# MStar-WLAN.net
KiCad netlist of a schematic drawn in EAGLE
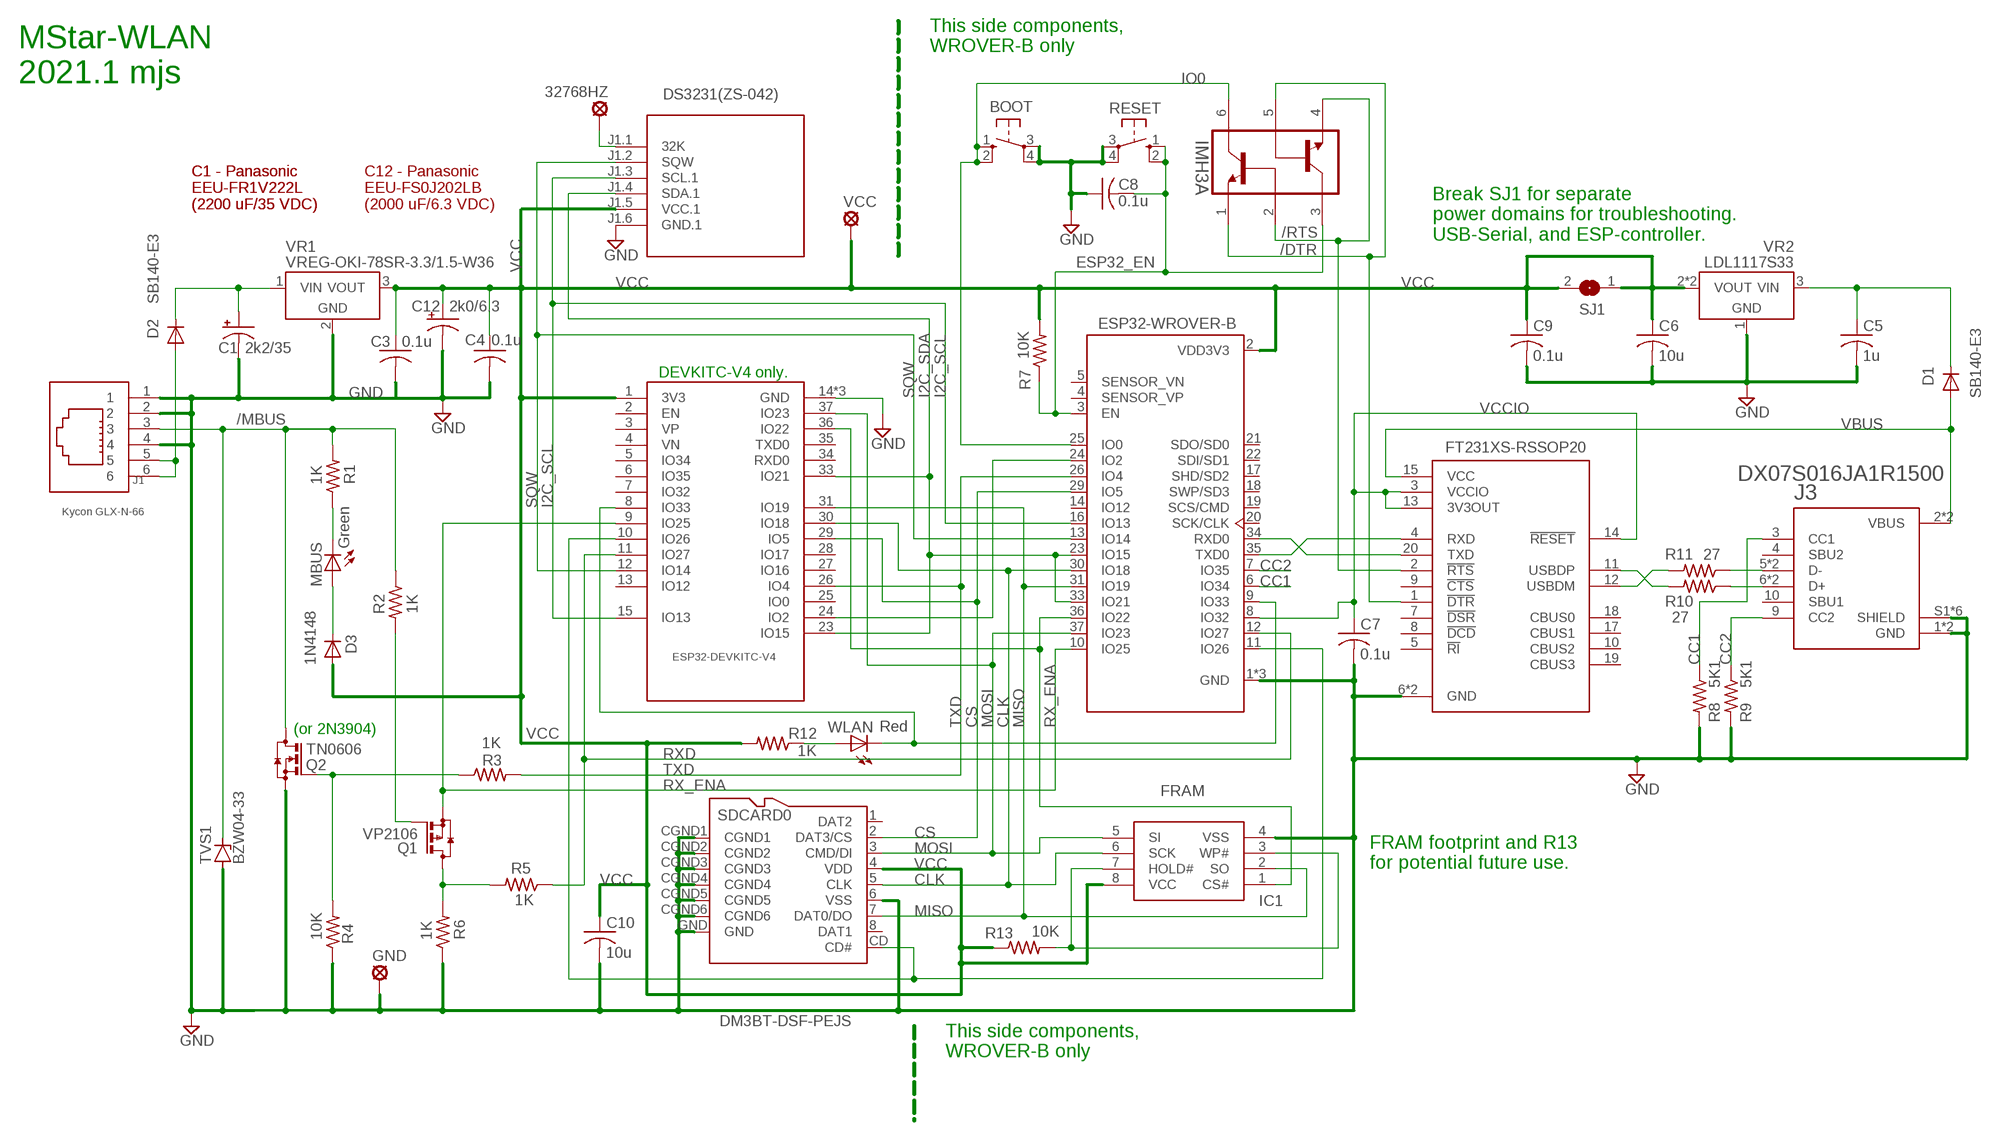
[diagram p0: schematic, sheet 1]

(export (version "E")
  (design (tool "Eeschema 10.0.6"))
  (components
    (comp (ref "32768HZ")
      (value "MCS10B")
      (footprint "eagle-import:MCS10B")
      (libsource (lib "eagle-import") (part "MCS10B"))
    )
    (comp (ref "BOOT")
      (value "PTS645SM432LFS")
      (footprint "eagle-import:B3F-10XX")
      (fields (field (name "MPN") "B3F-1000"))
      (libsource (lib "eagle-import") (part "10-XX"))
    )
    (comp (ref "C1")
      (value "2k2/35")
      (footprint "eagle-import:E5-4")
      (libsource (lib "eagle-import") (part "CPOL-USE5-4"))
    )
    (comp (ref "C3")
      (value "0.1u")
      (footprint "eagle-import:C025-024X044")
      (libsource (lib "eagle-import") (part "C-US025-024X044"))
    )
    (comp (ref "C4")
      (value "0.1u")
      (footprint "eagle-import:C025-024X044")
      (libsource (lib "eagle-import") (part "C-US025-024X044"))
    )
    (comp (ref "C5")
      (value "1u")
      (footprint "eagle-import:C1206")
      (libsource (lib "eagle-import") (part "C-USC1206"))
    )
    (comp (ref "C6")
      (value "10u")
      (footprint "eagle-import:C1206")
      (libsource (lib "eagle-import") (part "C-USC1206"))
    )
    (comp (ref "C7")
      (value "0.1u")
      (footprint "eagle-import:C025-024X044")
      (libsource (lib "eagle-import") (part "C-US025-024X044"))
    )
    (comp (ref "C8")
      (value "0.1u")
      (footprint "eagle-import:C025-024X044")
      (libsource (lib "eagle-import") (part "C-US025-024X044"))
    )
    (comp (ref "C9")
      (value "0.1u")
      (footprint "eagle-import:C025-024X044")
      (libsource (lib "eagle-import") (part "C-US025-024X044"))
    )
    (comp (ref "C10")
      (value "10u")
      (footprint "eagle-import:C1206")
      (libsource (lib "eagle-import") (part "C-USC1206"))
    )
    (comp (ref "C12")
      (value "2k0/6.3")
      (footprint "eagle-import:E5-6")
      (libsource (lib "eagle-import") (part "CPOL-USE5-6"))
    )
    (comp (ref "D1")
      (value "SB140-E3")
      (footprint "eagle-import:DO41-7.6")
      (libsource (lib "eagle-import") (part "DIODE-DO41-7.6"))
    )
    (comp (ref "D2")
      (value "SB140-E3")
      (footprint "eagle-import:DO41-7.6")
      (libsource (lib "eagle-import") (part "DIODE-DO41-7.6"))
    )
    (comp (ref "D3")
      (value "1N4148")
      (footprint "eagle-import:DO35-7")
      (libsource (lib "eagle-import") (part "1N4148DO35-7"))
    )
    (comp (ref "DS3231(ZS-042)")
      (value "RTC-DS3231-AT24C32-6")
      (footprint "eagle-import:RTC-DS3231-AT24C32-6")
      (libsource (lib "eagle-import") (part "RTC-DS3231-AT24C32-6"))
    )
    (comp (ref "ESP32-WROVER-B")
      (value "ESP32-WROVER-I")
      (footprint "eagle-import:XCVR_ESP32-WROVER-I")
      (fields (field (name "MF") "Espressif Systems"))
      (libsource (lib "eagle-import") (part "ESP32-WROVER-I"))
    )
    (comp (ref "FT231XS")
      (value "FT231XS-RSSOP20")
      (footprint "eagle-import:SSOP20")
      (fields
        (field (name "DIGI-KEY_PART_NUMBER") "768-1129-1-ND")
        (field (name "MF") "FTDI,")
        (field (name "MP") "FT231XS-R")
      )
      (libsource (lib "eagle-import") (part "FT231XS-RSSOP20"))
    )
    (comp (ref "GND")
      (value "MCS10B")
      (footprint "eagle-import:MCS10B")
      (libsource (lib "eagle-import") (part "MCS10B"))
    )
    (comp (ref "IC1")
      (value "FRAM")
      (footprint "eagle-import:SO-08M")
      (libsource (lib "eagle-import") (part "MR45V100AMAZAATLSO8M"))
    )
    (comp (ref "IMH3A")
      (value "IMH3ATSOP6")
      (footprint "eagle-import:TSOP6")
      (libsource (lib "eagle-import") (part "IMH3ATSOP6"))
    )
    (comp (ref "J1")
      (value "Kycon GLX-N-66")
      (footprint "eagle-import:6P6C")
      (libsource (lib "eagle-import") (part "6P6C"))
    )
    (comp (ref "J3")
      (value "DX07S016JA1R1500")
      (footprint "eagle-import:JAE_DX07S016JA1R1500")
      (fields (field (name "MF") "JAE Electronics"))
      (libsource (lib "eagle-import") (part "DX07S016JA1R1500"))
    )
    (comp (ref "MBUS")
      (value "Green")
      (footprint "eagle-import:LED3MM")
      (libsource (lib "eagle-import") (part "LED3MM"))
    )
    (comp (ref "Q1")
      (value "VP2106")
      (footprint "eagle-import:TO92")
      (libsource (lib "eagle-import") (part "VP2106"))
    )
    (comp (ref "Q2")
      (value "TN0606")
      (footprint "eagle-import:TO92")
      (libsource (lib "eagle-import") (part "TN0606"))
    )
    (comp (ref "R1")
      (value "1K")
      (footprint "eagle-import:0204_5")
      (libsource (lib "eagle-import") (part "R-US_"))
    )
    (comp (ref "R2")
      (value "1K")
      (footprint "eagle-import:0204_5")
      (libsource (lib "eagle-import") (part "R-US_"))
    )
    (comp (ref "R3")
      (value "1K")
      (footprint "eagle-import:0204_5")
      (libsource (lib "eagle-import") (part "R-US_"))
    )
    (comp (ref "R4")
      (value "10K")
      (footprint "eagle-import:0204_5")
      (libsource (lib "eagle-import") (part "R-US_"))
    )
    (comp (ref "R5")
      (value "1K")
      (footprint "eagle-import:0204_5")
      (libsource (lib "eagle-import") (part "R-US_"))
    )
    (comp (ref "R6")
      (value "1K")
      (footprint "eagle-import:0204_5")
      (libsource (lib "eagle-import") (part "R-US_"))
    )
    (comp (ref "R7")
      (value "10K")
      (footprint "eagle-import:0204_5")
      (libsource (lib "eagle-import") (part "R-US_"))
    )
    (comp (ref "R8")
      (value "5K1")
      (footprint "eagle-import:0204_5")
      (libsource (lib "eagle-import") (part "R-US_"))
    )
    (comp (ref "R9")
      (value "5K1")
      (footprint "eagle-import:0204_5")
      (libsource (lib "eagle-import") (part "R-US_"))
    )
    (comp (ref "R10")
      (value "27")
      (footprint "eagle-import:0204_5")
      (libsource (lib "eagle-import") (part "R-US_"))
    )
    (comp (ref "R11")
      (value "27")
      (footprint "eagle-import:0204_5")
      (libsource (lib "eagle-import") (part "R-US_"))
    )
    (comp (ref "R12")
      (value "1K")
      (footprint "eagle-import:0204_5")
      (libsource (lib "eagle-import") (part "R-US_"))
    )
    (comp (ref "R13")
      (value "10K")
      (footprint "eagle-import:R1206")
      (libsource (lib "eagle-import") (part "R-US_R1206"))
    )
    (comp (ref "RESET")
      (value "PTS645SM432LFS")
      (footprint "eagle-import:B3F-10XX")
      (fields (field (name "MPN") "B3F-1000"))
      (libsource (lib "eagle-import") (part "10-XX"))
    )
    (comp (ref "SDCARD0")
      (value "DM3BT-DSF-PEJS")
      (footprint "eagle-import:DM3BT-DSF-PEJS")
      (fields (field (name "MF") "Hirose"))
      (libsource (lib "eagle-import") (part "DM3BT-DSF-PEJS"))
    )
    (comp (ref "SJ1") (value "SJ") (footprint "eagle-import:SJ") (libsource (lib "eagle-import") (part "SJ")))
    (comp (ref "TVS1")
      (value "BZW04-33")
      (footprint "eagle-import:DO41Z10")
      (libsource (lib "eagle-import") (part "ZPY"))
    )
    (comp (ref "U$1")
      (value "ESP32-DEVKITC-V4-NOSD")
      (footprint "eagle-import:ESP32-DEVKITC-V4-NOSD")
      (libsource (lib "eagle-import") (part "ESP32-DEVKITC-V4-NOSD"))
    )
    (comp (ref "VCC")
      (value "MCS10B")
      (footprint "eagle-import:MCS10B")
      (libsource (lib "eagle-import") (part "MCS10B"))
    )
    (comp (ref "VR1")
      (value "VREG-OKI-78SR-3.3/1.5-W36")
      (footprint "eagle-import:OKI-78SR")
      (libsource (lib "eagle-import") (part "VREG-OKI-78SR-3.3/1.5-W36"))
    )
    (comp (ref "VR2")
      (value "LDL1117S33")
      (footprint "eagle-import:SOT223")
      (libsource (lib "eagle-import") (part "VREG-TS1117CW-3V3"))
    )
    (comp (ref "WLAN")
      (value "Red")
      (footprint "eagle-import:LED3MM")
      (libsource (lib "eagle-import") (part "LED3MM"))
    )
  )
  (nets
    (net (code "1") (name "/CC1") (class "Default")
      (node (ref "ESP32-WROVER-B") (pin "6") (pinfunction "IO34_6") (pintype "input"))
      (node (ref "J3") (pin "3") (pinfunction "CC1_3") (pintype "passive"))
      (node (ref "R8") (pin "1") (pinfunction "1_1") (pintype "passive"))
    )
    (net (code "2") (name "/CC2") (class "Default")
      (node (ref "ESP32-WROVER-B") (pin "7") (pinfunction "IO35_7") (pintype "input"))
      (node (ref "J3") (pin "9") (pinfunction "CC2_9") (pintype "passive"))
      (node (ref "R9") (pin "1") (pinfunction "1_1") (pintype "passive"))
    )
    (net (code "3") (name "/CLK") (class "Default")
      (node (ref "ESP32-WROVER-B") (pin "30") (pinfunction "IO18_30") (pintype "bidirectional"))
      (node (ref "IC1") (pin "6") (pinfunction "SCK_6") (pintype "bidirectional"))
      (node (ref "SDCARD0") (pin "5") (pinfunction "CLK_5") (pintype "bidirectional"))
      (node (ref "U$1") (pin "30") (pinfunction "IO18_30") (pintype "bidirectional"))
    )
    (net (code "4") (name "/CS") (class "Default")
      (node (ref "ESP32-WROVER-B") (pin "29") (pinfunction "IO5_29") (pintype "bidirectional"))
      (node (ref "SDCARD0") (pin "2") (pinfunction "DAT3/CS_2") (pintype "bidirectional"))
      (node (ref "U$1") (pin "29") (pinfunction "IO5_29") (pintype "bidirectional"))
    )
    (net (code "5") (name "/ESP32_EN") (class "Default")
      (node (ref "C8") (pin "2") (pinfunction "2_2") (pintype "passive"))
      (node (ref "ESP32-WROVER-B") (pin "3") (pinfunction "EN_3") (pintype "input"))
      (node (ref "IMH3A") (pin "3") (pinfunction "Q2C_3") (pintype "bidirectional"))
      (node (ref "R7") (pin "1") (pinfunction "1_1") (pintype "passive"))
      (node (ref "RESET") (pin "1") (pinfunction "S_1") (pintype "passive"))
      (node (ref "RESET") (pin "2") (pinfunction "S1_2") (pintype "passive"))
    )
    (net (code "6") (name "/I2C_SCL") (class "Default")
      (node (ref "DS3231(ZS-042)") (pin "J1.3") (pinfunction "SCL.1_J1.3") (pintype "bidirectional"))
      (node (ref "ESP32-WROVER-B") (pin "16") (pinfunction "IO13_16") (pintype "bidirectional"))
      (node (ref "U$1") (pin "15") (pinfunction "IO13_15") (pintype "bidirectional"))
    )
    (net (code "7") (name "/I2C_SDA") (class "Default")
      (node (ref "DS3231(ZS-042)") (pin "J1.4") (pinfunction "SDA.1_J1.4") (pintype "bidirectional"))
      (node (ref "ESP32-WROVER-B") (pin "23") (pinfunction "IO15_23") (pintype "bidirectional"))
      (node (ref "ESP32-WROVER-B") (pin "33") (pinfunction "IO21_33") (pintype "bidirectional"))
      (node (ref "U$1") (pin "23") (pinfunction "IO15_23") (pintype "bidirectional"))
      (node (ref "U$1") (pin "33") (pinfunction "IO21_33") (pintype "bidirectional"))
    )
    (net (code "8") (name "/IO0") (class "Default")
      (node (ref "BOOT") (pin "1") (pinfunction "S_1") (pintype "passive"))
      (node (ref "BOOT") (pin "2") (pinfunction "S1_2") (pintype "passive"))
      (node (ref "ESP32-WROVER-B") (pin "25") (pinfunction "IO0_25") (pintype "bidirectional"))
      (node (ref "IMH3A") (pin "6") (pinfunction "Q1C_6") (pintype "bidirectional"))
    )
    (net (code "9") (name "/MISO") (class "Default")
      (node (ref "ESP32-WROVER-B") (pin "31") (pinfunction "IO19_31") (pintype "bidirectional"))
      (node (ref "IC1") (pin "2") (pinfunction "SO_2") (pintype "bidirectional"))
      (node (ref "SDCARD0") (pin "7") (pinfunction "DAT0/DO_7") (pintype "bidirectional"))
      (node (ref "U$1") (pin "31") (pinfunction "IO19_31") (pintype "bidirectional"))
    )
    (net (code "10") (name "/MOSI") (class "Default")
      (node (ref "ESP32-WROVER-B") (pin "37") (pinfunction "IO23_37") (pintype "bidirectional"))
      (node (ref "IC1") (pin "5") (pinfunction "SI_5") (pintype "bidirectional"))
      (node (ref "SDCARD0") (pin "3") (pinfunction "CMD/DI_3") (pintype "bidirectional"))
      (node (ref "U$1") (pin "37") (pinfunction "IO23_37") (pintype "bidirectional"))
    )
    (net (code "12") (name "/RXD") (class "Default")
      (node (ref "ESP32-WROVER-B") (pin "12") (pinfunction "IO27_12") (pintype "bidirectional"))
      (node (ref "R5") (pin "1") (pinfunction "1_1") (pintype "passive"))
      (node (ref "U$1") (pin "11") (pinfunction "IO27_11") (pintype "bidirectional"))
    )
    (net (code "13") (name "/RX_ENA") (class "Default")
      (node (ref "ESP32-WROVER-B") (pin "10") (pinfunction "IO25_10") (pintype "bidirectional"))
      (node (ref "Q1") (pin "S") (pinfunction "S_S") (pintype "passive"))
      (node (ref "U$1") (pin "9") (pinfunction "IO25_9") (pintype "bidirectional"))
    )
    (net (code "14") (name "/SQW") (class "Default")
      (node (ref "DS3231(ZS-042)") (pin "J1.2") (pinfunction "SQW_J1.2") (pintype "bidirectional"))
      (node (ref "ESP32-WROVER-B") (pin "13") (pinfunction "IO14_13") (pintype "bidirectional"))
      (node (ref "U$1") (pin "12") (pinfunction "IO14_12") (pintype "bidirectional"))
    )
    (net (code "15") (name "/TXD") (class "Default")
      (node (ref "ESP32-WROVER-B") (pin "26") (pinfunction "IO4_26") (pintype "bidirectional"))
      (node (ref "R3") (pin "2") (pinfunction "2_2") (pintype "passive"))
      (node (ref "U$1") (pin "26") (pinfunction "IO4_26") (pintype "bidirectional"))
    )
    (net (code "16") (name "/VBUS") (class "Default")
      (node (ref "D1") (pin "A") (pinfunction "A_A") (pintype "passive"))
      (node (ref "FT231XS") (pin "15") (pinfunction "VCC_15") (pintype "power_in"))
      (node (ref "J3") (pin "11") (pinfunction "VBUS_11") (pintype "power_in"))
      (node (ref "J3") (pin "2") (pinfunction "VBUS_2") (pintype "power_in"))
    )
    (net (code "17") (name "/VCC") (class "Default")
      (node (ref "C10") (pin "1") (pinfunction "1_1") (pintype "passive"))
      (node (ref "C12") (pin "+") (pinfunction "+_+") (pintype "passive"))
      (node (ref "C3") (pin "1") (pinfunction "1_1") (pintype "passive"))
      (node (ref "C4") (pin "1") (pinfunction "1_1") (pintype "passive"))
      (node (ref "C6") (pin "1") (pinfunction "1_1") (pintype "passive"))
      (node (ref "C9") (pin "1") (pinfunction "1_1") (pintype "passive"))
      (node (ref "D3") (pin "A") (pinfunction "A_A") (pintype "passive"))
      (node (ref "DS3231(ZS-042)") (pin "J1.5") (pinfunction "VCC.1_J1.5") (pintype "power_in"))
      (node (ref "ESP32-WROVER-B") (pin "2") (pinfunction "VDD3V3_2") (pintype "power_in"))
      (node (ref "IC1") (pin "8") (pinfunction "VCC_8") (pintype "bidirectional"))
      (node (ref "R12") (pin "2") (pinfunction "2_2") (pintype "passive"))
      (node (ref "R13") (pin "1") (pinfunction "1_1") (pintype "passive"))
      (node (ref "R7") (pin "2") (pinfunction "2_2") (pintype "passive"))
      (node (ref "SDCARD0") (pin "4") (pinfunction "VDD_4") (pintype "bidirectional"))
      (node (ref "SJ1") (pin "1") (pinfunction "1_1") (pintype "passive"))
      (node (ref "SJ1") (pin "2") (pinfunction "2_2") (pintype "passive"))
      (node (ref "U$1") (pin "1") (pinfunction "3V3_1") (pintype "power_in"))
      (node (ref "VCC") (pin "MP") (pinfunction "MP_MP") (pintype "passive"))
      (node (ref "VR1") (pin "3") (pinfunction "VOUT_3") (pintype "power_in"))
      (node (ref "VR2") (pin "2") (pinfunction "VOUT_2") (pintype "power_in"))
      (node (ref "VR2") (pin "4") (pinfunction "VOUT_4") (pintype "power_in"))
    )
    (net (code "18") (name "/VCCIO") (class "Default")
      (node (ref "C7") (pin "1") (pinfunction "1_1") (pintype "passive"))
      (node (ref "ESP32-WROVER-B") (pin "8") (pinfunction "IO32_8") (pintype "bidirectional"))
      (node (ref "FT231XS") (pin "13") (pinfunction "3V3OUT_13") (pintype "power_in"))
      (node (ref "FT231XS") (pin "14") (pinfunction "~{RESET}_14") (pintype "input"))
      (node (ref "FT231XS") (pin "3") (pinfunction "VCCIO_3") (pintype "power_in"))
    )
    (net (code "19") (name "/{slash}DTR") (class "Default")
      (node (ref "FT231XS") (pin "1") (pinfunction "~{DTR}_1") (pintype "output"))
      (node (ref "IMH3A") (pin "1") (pinfunction "Q1E_1") (pintype "bidirectional"))
      (node (ref "IMH3A") (pin "5") (pinfunction "Q2B_5") (pintype "bidirectional"))
    )
    (net (code "20") (name "/{slash}MBUS") (class "Default")
      (node (ref "J1") (pin "3") (pinfunction "3_3") (pintype "passive"))
      (node (ref "Q2") (pin "D") (pinfunction "D_D") (pintype "passive"))
      (node (ref "R1") (pin "2") (pinfunction "2_2") (pintype "passive"))
      (node (ref "R2") (pin "1") (pinfunction "1_1") (pintype "passive"))
      (node (ref "TVS1") (pin "C") (pinfunction "C_C") (pintype "passive"))
    )
    (net (code "21") (name "/{slash}RTS") (class "Default")
      (node (ref "FT231XS") (pin "2") (pinfunction "~{RTS}_2") (pintype "output"))
      (node (ref "IMH3A") (pin "2") (pinfunction "Q1B_2") (pintype "bidirectional"))
      (node (ref "IMH3A") (pin "4") (pinfunction "Q2E_4") (pintype "bidirectional"))
    )
    (net (code "22") (name "GND") (class "Default")
      (node (ref "BOOT") (pin "3") (pinfunction "P_3") (pintype "passive"))
      (node (ref "BOOT") (pin "4") (pinfunction "P1_4") (pintype "passive"))
      (node (ref "C1") (pin "-") (pinfunction "-_-") (pintype "passive"))
      (node (ref "C10") (pin "2") (pinfunction "2_2") (pintype "passive"))
      (node (ref "C12") (pin "-") (pinfunction "-_-") (pintype "passive"))
      (node (ref "C3") (pin "2") (pinfunction "2_2") (pintype "passive"))
      (node (ref "C4") (pin "2") (pinfunction "2_2") (pintype "passive"))
      (node (ref "C5") (pin "2") (pinfunction "2_2") (pintype "passive"))
      (node (ref "C6") (pin "2") (pinfunction "2_2") (pintype "passive"))
      (node (ref "C7") (pin "2") (pinfunction "2_2") (pintype "passive"))
      (node (ref "C8") (pin "1") (pinfunction "1_1") (pintype "passive"))
      (node (ref "C9") (pin "2") (pinfunction "2_2") (pintype "passive"))
      (node (ref "DS3231(ZS-042)") (pin "J1.6") (pinfunction "GND.1_J1.6") (pintype "power_in"))
      (node (ref "ESP32-WROVER-B") (pin "1") (pinfunction "GND_1") (pintype "power_in"))
      (node (ref "ESP32-WROVER-B") (pin "15") (pinfunction "GND_15") (pintype "power_in"))
      (node (ref "ESP32-WROVER-B") (pin "38") (pinfunction "GND_38") (pintype "power_in"))
      (node (ref "FT231XS") (pin "16") (pinfunction "GND_16") (pintype "power_in"))
      (node (ref "FT231XS") (pin "6") (pinfunction "GND_6") (pintype "power_in"))
      (node (ref "GND") (pin "MP") (pinfunction "MP_MP") (pintype "passive"))
      (node (ref "IC1") (pin "4") (pinfunction "VSS_4") (pintype "bidirectional"))
      (node (ref "J1") (pin "1") (pinfunction "1_1") (pintype "passive"))
      (node (ref "J1") (pin "2") (pinfunction "2_2") (pintype "passive"))
      (node (ref "J1") (pin "4") (pinfunction "4_4") (pintype "passive"))
      (node (ref "J3") (pin "1") (pinfunction "GND_1") (pintype "power_in"))
      (node (ref "J3") (pin "12") (pinfunction "GND_12") (pintype "power_in"))
      (node (ref "J3") (pin "S1") (pinfunction "SHIELD_S1") (pintype "passive"))
      (node (ref "J3") (pin "S2") (pinfunction "SHIELD_S2") (pintype "passive"))
      (node (ref "J3") (pin "S3") (pinfunction "SHIELD_S3") (pintype "passive"))
      (node (ref "J3") (pin "S4") (pinfunction "SHIELD_S4") (pintype "passive"))
      (node (ref "J3") (pin "S5") (pinfunction "SHIELD_S5") (pintype "passive"))
      (node (ref "J3") (pin "S6") (pinfunction "SHIELD_S6") (pintype "passive"))
      (node (ref "Q2") (pin "S") (pinfunction "S_S") (pintype "passive"))
      (node (ref "R4") (pin "1") (pinfunction "1_1") (pintype "passive"))
      (node (ref "R6") (pin "1") (pinfunction "1_1") (pintype "passive"))
      (node (ref "R8") (pin "2") (pinfunction "2_2") (pintype "passive"))
      (node (ref "R9") (pin "2") (pinfunction "2_2") (pintype "passive"))
      (node (ref "RESET") (pin "3") (pinfunction "P_3") (pintype "passive"))
      (node (ref "RESET") (pin "4") (pinfunction "P1_4") (pintype "passive"))
      (node (ref "SDCARD0") (pin "6") (pinfunction "VSS_6") (pintype "bidirectional"))
      (node (ref "SDCARD0") (pin "CGND1") (pinfunction "CGND1_CGND1") (pintype "bidirectional"))
      (node (ref "SDCARD0") (pin "CGND2") (pinfunction "CGND2_CGND2") (pintype "bidirectional"))
      (node (ref "SDCARD0") (pin "CGND3") (pinfunction "CGND3_CGND3") (pintype "bidirectional"))
      (node (ref "SDCARD0") (pin "CGND4") (pinfunction "CGND4_CGND4") (pintype "bidirectional"))
      (node (ref "SDCARD0") (pin "CGND5") (pinfunction "CGND5_CGND5") (pintype "bidirectional"))
      (node (ref "SDCARD0") (pin "CGND6") (pinfunction "CGND6_CGND6") (pintype "bidirectional"))
      (node (ref "SDCARD0") (pin "GND") (pinfunction "GND_GND") (pintype "bidirectional"))
      (node (ref "TVS1") (pin "A") (pinfunction "A_A") (pintype "passive"))
      (node (ref "U$1") (pin "14") (pinfunction "GND_14") (pintype "power_in"))
      (node (ref "U$1") (pin "32") (pinfunction "GND_32") (pintype "power_in"))
      (node (ref "U$1") (pin "38") (pinfunction "GND_38") (pintype "power_in"))
      (node (ref "VR1") (pin "2") (pinfunction "GND_2") (pintype "power_in"))
      (node (ref "VR2") (pin "1") (pinfunction "GND_1") (pintype "power_in"))
    )
    (net (code "23") (name "Net-(D2-PadA)") (class "Default")
      (node (ref "D2") (pin "A") (pinfunction "A_A") (pintype "passive"))
      (node (ref "J1") (pin "5") (pinfunction "5_5") (pintype "passive"))
      (node (ref "J1") (pin "6") (pinfunction "6_6") (pintype "passive"))
    )
    (net (code "24") (name "Net-(D3-PadC)") (class "Default")
      (node (ref "D3") (pin "C") (pinfunction "C_C") (pintype "passive"))
      (node (ref "MBUS") (pin "A") (pinfunction "A_A") (pintype "passive"))
    )
    (net (code "25") (name "Net-(DS3231(ZS-042)-32K)") (class "Default")
      (node (ref "32768HZ") (pin "MP") (pinfunction "MP_MP") (pintype "passive"))
      (node (ref "DS3231(ZS-042)") (pin "J1.1") (pinfunction "32K_J1.1") (pintype "bidirectional"))
    )
    (net (code "26") (name "Net-(ESP32-WROVER-B-IO2)") (class "Default")
      (node (ref "ESP32-WROVER-B") (pin "24") (pinfunction "IO2_24") (pintype "bidirectional"))
      (node (ref "U$1") (pin "24") (pinfunction "IO2_24") (pintype "bidirectional"))
    )
    (net (code "27") (name "Net-(ESP32-WROVER-B-IO22)") (class "Default")
      (node (ref "ESP32-WROVER-B") (pin "36") (pinfunction "IO22_36") (pintype "bidirectional"))
      (node (ref "IC1") (pin "1") (pinfunction "CS#_1") (pintype "bidirectional"))
      (node (ref "U$1") (pin "36") (pinfunction "IO22_36") (pintype "bidirectional"))
    )
    (net (code "28") (name "Net-(ESP32-WROVER-B-IO26)") (class "Default")
      (node (ref "ESP32-WROVER-B") (pin "11") (pinfunction "IO26_11") (pintype "bidirectional"))
      (node (ref "SDCARD0") (pin "CD") (pinfunction "CD#_CD") (pintype "bidirectional"))
      (node (ref "U$1") (pin "10") (pinfunction "IO26_10") (pintype "bidirectional"))
    )
    (net (code "29") (name "Net-(ESP32-WROVER-B-IO33)") (class "Default")
      (node (ref "ESP32-WROVER-B") (pin "9") (pinfunction "IO33_9") (pintype "bidirectional"))
      (node (ref "U$1") (pin "8") (pinfunction "IO33_8") (pintype "bidirectional"))
      (node (ref "WLAN") (pin "K") (pinfunction "C_K") (pintype "passive"))
    )
    (net (code "30") (name "Net-(ESP32-WROVER-B-RXD0)") (class "Default")
      (node (ref "ESP32-WROVER-B") (pin "34") (pinfunction "RXD0_34") (pintype "bidirectional"))
      (node (ref "FT231XS") (pin "20") (pinfunction "TXD_20") (pintype "output"))
    )
    (net (code "31") (name "Net-(ESP32-WROVER-B-TXD0)") (class "Default")
      (node (ref "ESP32-WROVER-B") (pin "35") (pinfunction "TXD0_35") (pintype "bidirectional"))
      (node (ref "FT231XS") (pin "4") (pinfunction "RXD_4") (pintype "input"))
    )
    (net (code "32") (name "Net-(FT231XS-USBDM)") (class "Default")
      (node (ref "FT231XS") (pin "12") (pinfunction "USBDM_12") (pintype "input"))
      (node (ref "R11") (pin "2") (pinfunction "2_2") (pintype "passive"))
    )
    (net (code "33") (name "Net-(FT231XS-USBDP)") (class "Default")
      (node (ref "FT231XS") (pin "11") (pinfunction "USBDP_11") (pintype "input"))
      (node (ref "R10") (pin "2") (pinfunction "2_2") (pintype "passive"))
    )
    (net (code "34") (name "Net-(IC1-HOLD#)") (class "Default")
      (node (ref "IC1") (pin "3") (pinfunction "WP#_3") (pintype "bidirectional"))
      (node (ref "IC1") (pin "7") (pinfunction "HOLD#_7") (pintype "bidirectional"))
      (node (ref "R13") (pin "2") (pinfunction "2_2") (pintype "passive"))
    )
    (net (code "35") (name "Net-(J3-D+-Pad6)") (class "Default")
      (node (ref "J3") (pin "6") (pinfunction "D+_6") (pintype "passive"))
      (node (ref "J3") (pin "7") (pinfunction "D+_7") (pintype "passive"))
      (node (ref "R10") (pin "1") (pinfunction "1_1") (pintype "passive"))
    )
    (net (code "36") (name "Net-(J3-D--Pad5)") (class "Default")
      (node (ref "J3") (pin "5") (pinfunction "D-_5") (pintype "passive"))
      (node (ref "J3") (pin "8") (pinfunction "D-_8") (pintype "passive"))
      (node (ref "R11") (pin "1") (pinfunction "1_1") (pintype "passive"))
    )
    (net (code "37") (name "Net-(MBUS-C)") (class "Default")
      (node (ref "MBUS") (pin "K") (pinfunction "C_K") (pintype "passive"))
      (node (ref "R1") (pin "1") (pinfunction "1_1") (pintype "passive"))
    )
    (net (code "38") (name "Net-(Q1-PadD)") (class "Default")
      (node (ref "Q1") (pin "D") (pinfunction "D_D") (pintype "passive"))
      (node (ref "R5") (pin "2") (pinfunction "2_2") (pintype "passive"))
      (node (ref "R6") (pin "2") (pinfunction "2_2") (pintype "passive"))
    )
    (net (code "39") (name "Net-(Q1-PadG)") (class "Default")
      (node (ref "Q1") (pin "G") (pinfunction "G_G") (pintype "passive"))
      (node (ref "R2") (pin "2") (pinfunction "2_2") (pintype "passive"))
    )
    (net (code "40") (name "Net-(Q2-PadG)") (class "Default")
      (node (ref "Q2") (pin "G") (pinfunction "G_G") (pintype "passive"))
      (node (ref "R3") (pin "1") (pinfunction "1_1") (pintype "passive"))
      (node (ref "R4") (pin "2") (pinfunction "2_2") (pintype "passive"))
    )
    (net (code "41") (name "Net-(R12-Pad1)") (class "Default")
      (node (ref "R12") (pin "1") (pinfunction "1_1") (pintype "passive"))
      (node (ref "WLAN") (pin "A") (pinfunction "A_A") (pintype "passive"))
    )
    (net (code "42") (name "Net-(VR1-VIN)") (class "Default")
      (node (ref "C1") (pin "+") (pinfunction "+_+") (pintype "passive"))
      (node (ref "D2") (pin "C") (pinfunction "C_C") (pintype "passive"))
      (node (ref "VR1") (pin "1") (pinfunction "VIN_1") (pintype "power_in"))
    )
    (net (code "43") (name "Net-(VR2-VIN)") (class "Default")
      (node (ref "C5") (pin "1") (pinfunction "1_1") (pintype "passive"))
      (node (ref "D1") (pin "C") (pinfunction "C_C") (pintype "passive"))
      (node (ref "VR2") (pin "3") (pinfunction "VIN_3") (pintype "power_in"))
    )
    (net (code "44") (name "unconnected-(ESP32-WROVER-B-IO12-Pad14)") (class "Default")
      (node (ref "ESP32-WROVER-B") (pin "14") (pinfunction "IO12_14") (pintype "bidirectional"))
    )
    (net (code "45") (name "unconnected-(ESP32-WROVER-B-SCK{slash}CLK-Pad20)") (class "Default")
      (node (ref "ESP32-WROVER-B") (pin "20") (pinfunction "SCK/CLK_20") (pintype "bidirectional"))
    )
    (net (code "46") (name "unconnected-(ESP32-WROVER-B-SCS{slash}CMD-Pad19)") (class "Default")
      (node (ref "ESP32-WROVER-B") (pin "19") (pinfunction "SCS/CMD_19") (pintype "bidirectional"))
    )
    (net (code "47") (name "unconnected-(ESP32-WROVER-B-SDI{slash}SD1-Pad22)") (class "Default")
      (node (ref "ESP32-WROVER-B") (pin "22") (pinfunction "SDI/SD1_22") (pintype "bidirectional"))
    )
    (net (code "48") (name "unconnected-(ESP32-WROVER-B-SDO{slash}SD0-Pad21)") (class "Default")
      (node (ref "ESP32-WROVER-B") (pin "21") (pinfunction "SDO/SD0_21") (pintype "bidirectional"))
    )
    (net (code "49") (name "unconnected-(ESP32-WROVER-B-SENSOR_VN-Pad5)") (class "Default")
      (node (ref "ESP32-WROVER-B") (pin "5") (pinfunction "SENSOR_VN_5") (pintype "input"))
    )
    (net (code "50") (name "unconnected-(ESP32-WROVER-B-SENSOR_VP-Pad4)") (class "Default")
      (node (ref "ESP32-WROVER-B") (pin "4") (pinfunction "SENSOR_VP_4") (pintype "input"))
    )
    (net (code "51") (name "unconnected-(ESP32-WROVER-B-SHD{slash}SD2-Pad17)") (class "Default")
      (node (ref "ESP32-WROVER-B") (pin "17") (pinfunction "SHD/SD2_17") (pintype "bidirectional"))
    )
    (net (code "52") (name "unconnected-(ESP32-WROVER-B-SWP{slash}SD3-Pad18)") (class "Default")
      (node (ref "ESP32-WROVER-B") (pin "18") (pinfunction "SWP/SD3_18") (pintype "bidirectional"))
    )
    (net (code "53") (name "unconnected-(FT231XS-CBUS0-Pad18)") (class "Default")
      (node (ref "FT231XS") (pin "18") (pinfunction "CBUS0_18") (pintype "bidirectional"))
    )
    (net (code "54") (name "unconnected-(FT231XS-CBUS1-Pad17)") (class "Default")
      (node (ref "FT231XS") (pin "17") (pinfunction "CBUS1_17") (pintype "bidirectional"))
    )
    (net (code "55") (name "unconnected-(FT231XS-CBUS2-Pad10)") (class "Default")
      (node (ref "FT231XS") (pin "10") (pinfunction "CBUS2_10") (pintype "bidirectional"))
    )
    (net (code "56") (name "unconnected-(FT231XS-CBUS3-Pad19)") (class "Default")
      (node (ref "FT231XS") (pin "19") (pinfunction "CBUS3_19") (pintype "bidirectional"))
    )
    (net (code "57") (name "unconnected-(FT231XS-~{CTS}-Pad9)") (class "Default")
      (node (ref "FT231XS") (pin "9") (pinfunction "~{CTS}_9") (pintype "input"))
    )
    (net (code "58") (name "unconnected-(FT231XS-~{DCD}-Pad8)") (class "Default")
      (node (ref "FT231XS") (pin "8") (pinfunction "~{DCD}_8") (pintype "input"))
    )
    (net (code "59") (name "unconnected-(FT231XS-~{DSR}-Pad7)") (class "Default")
      (node (ref "FT231XS") (pin "7") (pinfunction "~{DSR}_7") (pintype "input"))
    )
    (net (code "60") (name "unconnected-(FT231XS-~{RI}-Pad5)") (class "Default")
      (node (ref "FT231XS") (pin "5") (pinfunction "~{RI}_5") (pintype "input"))
    )
    (net (code "61") (name "unconnected-(J3-SBU1-Pad10)") (class "Default")
      (node (ref "J3") (pin "10") (pinfunction "SBU1_10") (pintype "passive"))
    )
    (net (code "62") (name "unconnected-(J3-SBU2-Pad4)") (class "Default")
      (node (ref "J3") (pin "4") (pinfunction "SBU2_4") (pintype "passive"))
    )
    (net (code "63") (name "unconnected-(SDCARD0-DAT1-Pad8)") (class "Default")
      (node (ref "SDCARD0") (pin "8") (pinfunction "DAT1_8") (pintype "bidirectional"))
    )
    (net (code "64") (name "unconnected-(SDCARD0-DAT2-Pad1)") (class "Default")
      (node (ref "SDCARD0") (pin "1") (pinfunction "DAT2_1") (pintype "bidirectional"))
    )
    (net (code "65") (name "unconnected-(U$1-EN-Pad2)") (class "Default")
      (node (ref "U$1") (pin "2") (pinfunction "EN_2") (pintype "bidirectional"))
    )
    (net (code "66") (name "unconnected-(U$1-IO0-Pad25)") (class "Default")
      (node (ref "U$1") (pin "25") (pinfunction "IO0_25") (pintype "bidirectional"))
    )
    (net (code "67") (name "unconnected-(U$1-IO12-Pad13)") (class "Default")
      (node (ref "U$1") (pin "13") (pinfunction "IO12_13") (pintype "bidirectional"))
    )
    (net (code "68") (name "unconnected-(U$1-IO16-Pad27)") (class "Default")
      (node (ref "U$1") (pin "27") (pinfunction "IO16_27") (pintype "bidirectional"))
    )
    (net (code "69") (name "unconnected-(U$1-IO17-Pad28)") (class "Default")
      (node (ref "U$1") (pin "28") (pinfunction "IO17_28") (pintype "bidirectional"))
    )
    (net (code "70") (name "unconnected-(U$1-IO32-Pad7)") (class "Default")
      (node (ref "U$1") (pin "7") (pinfunction "IO32_7") (pintype "bidirectional"))
    )
    (net (code "71") (name "unconnected-(U$1-IO34-Pad5)") (class "Default")
      (node (ref "U$1") (pin "5") (pinfunction "IO34_5") (pintype "bidirectional"))
    )
    (net (code "72") (name "unconnected-(U$1-IO35-Pad6)") (class "Default")
      (node (ref "U$1") (pin "6") (pinfunction "IO35_6") (pintype "bidirectional"))
    )
    (net (code "73") (name "unconnected-(U$1-RXD0-Pad34)") (class "Default")
      (node (ref "U$1") (pin "34") (pinfunction "RXD0_34") (pintype "bidirectional"))
    )
    (net (code "74") (name "unconnected-(U$1-TXD0-Pad35)") (class "Default")
      (node (ref "U$1") (pin "35") (pinfunction "TXD0_35") (pintype "bidirectional"))
    )
    (net (code "75") (name "unconnected-(U$1-VN-Pad4)") (class "Default")
      (node (ref "U$1") (pin "4") (pinfunction "VN_4") (pintype "bidirectional"))
    )
    (net (code "76") (name "unconnected-(U$1-VP-Pad3)") (class "Default")
      (node (ref "U$1") (pin "3") (pinfunction "VP_3") (pintype "bidirectional"))
    )
  )
)
